# Display.net
KiCad netlist of a schematic drawn in Altium Designer
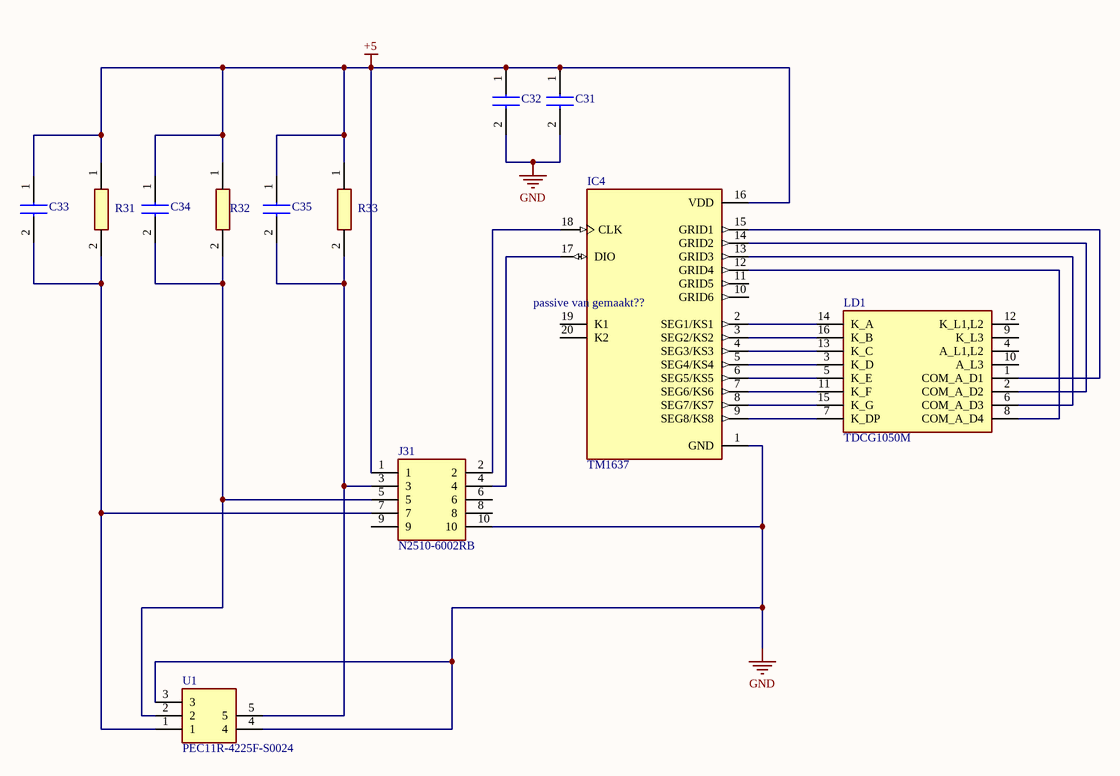
[diagram p0: Display.SchDoc]

(export (version "E")
  (design (tool "Eeschema 10.0.6"))
  (components
    (comp (ref "C31")
      (value "C0805C104K5RAC7411")
      (footprint "100nF")
      (description "Capacitor  100 uF 50VDC")
      (fields (field (name "MOUSER2 PART NUMBER") "80-C0805C104K5RACLR"))
      (libsource (lib "Schlib1") (part "C0805C104K5RAC7411"))
    )
    (comp (ref "C32")
      (value "C0805C104K5RAC7411")
      (footprint "100nF")
      (description "Capacitor  0.1 uF 50VDC")
      (fields (field (name "MOUSER2 PART NUMBER") "80-C0805C104K5RACLR"))
      (libsource (lib "Schlib1") (part "C0805C104K5RAC7411"))
    )
    (comp (ref "C33")
      (value "C0805C103K5TACAUTO")
      (footprint "10nF")
      (description "Capacitor 0.01µF 50VDC")
      (libsource (lib "Schlib1") (part "C0805C103K5TACAUTO"))
    )
    (comp (ref "C34")
      (value "C0805C103K5TACAUTO")
      (footprint "10nF")
      (description "Capacitor 0.01µF 50VDC")
      (libsource (lib "Schlib1") (part "C0805C103K5TACAUTO"))
    )
    (comp (ref "C35")
      (value "C0805C103K5TACAUTO")
      (footprint "10nF")
      (description "Capacitor 0.01µF 50VDC")
      (libsource (lib "Schlib1") (part "C0805C103K5TACAUTO"))
    )
    (comp (ref "IC4")
      (value "TM1637")
      (footprint "DisplayIC")
      (description "LED Drive Control Special Circuit")
      (fields (field (name "MF") "Titan Micro Electronics"))
      (libsource (lib "Schlib1") (part "TM1637"))
    )
    (comp (ref "J31")
      (value "N2510-6002RB")
      (footprint "SHDR10W64P254_2X5_2002X859X991P")
      (description "Connector")
      (fields (field (name "MOUSER2 PART NUMBER") "517-N2510-6002RB"))
      (libsource (lib "Schlib1") (part "N2510-6002RB"))
    )
    (comp (ref "LD1")
      (value "TDCG1050M")
      (footprint "NewPCBlib:Display")
      (description "Display")
      (fields (field (name "MOUSER2 PART NUMBER") "78-TDCG1050"))
      (libsource (lib "Schlib1") (part "TDCG1050M"))
    )
    (comp (ref "R31")
      (value "CRCW080510K0DHEAP")
      (footprint "Resistor")
      (description "Resistor 10KOhm")
      (libsource (lib "Schlib1") (part "CRCW080510K0DHEAP"))
    )
    (comp (ref "R32")
      (value "CRCW080510K0DHEAP")
      (footprint "Resistor")
      (description "Resistor 10KOhm")
      (libsource (lib "Schlib1") (part "CRCW080510K0DHEAP"))
    )
    (comp (ref "R33")
      (value "CRCW080510K0DHEAP")
      (footprint "Resistor")
      (description "Resistor 10KOhm")
      (libsource (lib "Schlib1") (part "CRCW080510K0DHEAP"))
    )
    (comp (ref "U1")
      (value "PEC11R-4225F-S0024")
      (footprint "PEC12R-4XXXF-SXXXX_1")
      (description "Undefined or Miscellaneous")
      (fields (field (name "MOUSER2 PART NUMBER") "652-PEC11R-4225F-S24"))
      (libsource (lib "Schlib1") (part "PEC11R-4225F-S0024"))
    )
  )
  (nets
    (net (code "1") (name "+5") (class "Default")
      (node (ref "C31") (pin "1") (pinfunction "1_1") (pintype "passive"))
      (node (ref "C32") (pin "1") (pinfunction "1_1") (pintype "passive"))
      (node (ref "C33") (pin "1") (pinfunction "1_1") (pintype "passive"))
      (node (ref "C34") (pin "1") (pinfunction "1_1") (pintype "passive"))
      (node (ref "C35") (pin "1") (pinfunction "1_1") (pintype "passive"))
      (node (ref "IC4") (pin "16") (pinfunction "VDD_16") (pintype "power_in"))
      (node (ref "J31") (pin "1") (pinfunction "1_1") (pintype "passive"))
      (node (ref "R31") (pin "1") (pinfunction "1_1") (pintype "passive"))
      (node (ref "R32") (pin "1") (pinfunction "1_1") (pintype "passive"))
      (node (ref "R33") (pin "1") (pinfunction "1_1") (pintype "passive"))
    )
    (net (code "2") (name "GND") (class "Default")
      (node (ref "C31") (pin "2") (pinfunction "2_2") (pintype "passive"))
      (node (ref "C32") (pin "2") (pinfunction "2_2") (pintype "passive"))
      (node (ref "IC4") (pin "1") (pinfunction "GND_1") (pintype "power_in"))
      (node (ref "J31") (pin "10") (pinfunction "10_10") (pintype "passive"))
      (node (ref "U1") (pin "3") (pinfunction "3_3") (pintype "passive"))
      (node (ref "U1") (pin "4") (pinfunction "4_4") (pintype "passive"))
    )
    (net (code "3") (name "Net-(C33-Pad2)") (class "Default")
      (node (ref "C33") (pin "2") (pinfunction "2_2") (pintype "passive"))
      (node (ref "J31") (pin "7") (pinfunction "7_7") (pintype "passive"))
      (node (ref "R31") (pin "2") (pinfunction "2_2") (pintype "passive"))
      (node (ref "U1") (pin "1") (pinfunction "1_1") (pintype "passive"))
    )
    (net (code "4") (name "Net-(C34-Pad2)") (class "Default")
      (node (ref "C34") (pin "2") (pinfunction "2_2") (pintype "passive"))
      (node (ref "J31") (pin "5") (pinfunction "5_5") (pintype "passive"))
      (node (ref "R32") (pin "2") (pinfunction "2_2") (pintype "passive"))
      (node (ref "U1") (pin "2") (pinfunction "2_2") (pintype "passive"))
    )
    (net (code "5") (name "Net-(C35-Pad2)") (class "Default")
      (node (ref "C35") (pin "2") (pinfunction "2_2") (pintype "passive"))
      (node (ref "J31") (pin "3") (pinfunction "3_3") (pintype "passive"))
      (node (ref "R33") (pin "2") (pinfunction "2_2") (pintype "passive"))
      (node (ref "U1") (pin "5") (pinfunction "5_5") (pintype "passive"))
    )
    (net (code "6") (name "Net-(IC4-CLK)") (class "Default")
      (node (ref "IC4") (pin "18") (pinfunction "CLK_18") (pintype "input"))
      (node (ref "J31") (pin "2") (pinfunction "2_2") (pintype "passive"))
    )
    (net (code "7") (name "Net-(IC4-DIO)") (class "Default")
      (node (ref "IC4") (pin "17") (pinfunction "DIO_17") (pintype "bidirectional"))
      (node (ref "J31") (pin "4") (pinfunction "4_4") (pintype "passive"))
    )
    (net (code "8") (name "Net-(IC4-GRID1)") (class "Default")
      (node (ref "IC4") (pin "15") (pinfunction "GRID1_15") (pintype "output"))
      (node (ref "LD1") (pin "1") (pinfunction "COM_A_D1_1") (pintype "passive"))
    )
    (net (code "9") (name "Net-(IC4-GRID2)") (class "Default")
      (node (ref "IC4") (pin "14") (pinfunction "GRID2_14") (pintype "output"))
      (node (ref "LD1") (pin "2") (pinfunction "COM_A_D2_2") (pintype "passive"))
    )
    (net (code "10") (name "Net-(IC4-GRID3)") (class "Default")
      (node (ref "IC4") (pin "13") (pinfunction "GRID3_13") (pintype "output"))
      (node (ref "LD1") (pin "6") (pinfunction "COM_A_D3_6") (pintype "passive"))
    )
    (net (code "11") (name "Net-(IC4-GRID4)") (class "Default")
      (node (ref "IC4") (pin "12") (pinfunction "GRID4_12") (pintype "output"))
      (node (ref "LD1") (pin "8") (pinfunction "COM_A_D4_8") (pintype "passive"))
    )
    (net (code "12") (name "Net-(IC4-SEG1{slash}KS1)") (class "Default")
      (node (ref "IC4") (pin "2") (pinfunction "SEG1/KS1_2") (pintype "output"))
      (node (ref "LD1") (pin "14") (pinfunction "K_A_14") (pintype "passive"))
    )
    (net (code "13") (name "Net-(IC4-SEG2{slash}KS2)") (class "Default")
      (node (ref "IC4") (pin "3") (pinfunction "SEG2/KS2_3") (pintype "output"))
      (node (ref "LD1") (pin "16") (pinfunction "K_B_16") (pintype "passive"))
    )
    (net (code "14") (name "Net-(IC4-SEG3{slash}KS3)") (class "Default")
      (node (ref "IC4") (pin "4") (pinfunction "SEG3/KS3_4") (pintype "output"))
      (node (ref "LD1") (pin "13") (pinfunction "K_C_13") (pintype "passive"))
    )
    (net (code "15") (name "Net-(IC4-SEG4{slash}KS4)") (class "Default")
      (node (ref "IC4") (pin "5") (pinfunction "SEG4/KS4_5") (pintype "output"))
      (node (ref "LD1") (pin "3") (pinfunction "K_D_3") (pintype "passive"))
    )
    (net (code "16") (name "Net-(IC4-SEG5{slash}KS5)") (class "Default")
      (node (ref "IC4") (pin "6") (pinfunction "SEG5/KS5_6") (pintype "output"))
      (node (ref "LD1") (pin "5") (pinfunction "K_E_5") (pintype "passive"))
    )
    (net (code "17") (name "Net-(IC4-SEG6{slash}KS6)") (class "Default")
      (node (ref "IC4") (pin "7") (pinfunction "SEG6/KS6_7") (pintype "output"))
      (node (ref "LD1") (pin "11") (pinfunction "K_F_11") (pintype "passive"))
    )
    (net (code "18") (name "Net-(IC4-SEG7{slash}KS7)") (class "Default")
      (node (ref "IC4") (pin "8") (pinfunction "SEG7/KS7_8") (pintype "output"))
      (node (ref "LD1") (pin "15") (pinfunction "K_G_15") (pintype "passive"))
    )
    (net (code "19") (name "Net-(IC4-SEG8{slash}KS8)") (class "Default")
      (node (ref "IC4") (pin "9") (pinfunction "SEG8/KS8_9") (pintype "output"))
      (node (ref "LD1") (pin "7") (pinfunction "K_DP_7") (pintype "passive"))
    )
    (net (code "20") (name "unconnected-(IC4-GRID5-Pad11)") (class "Default")
      (node (ref "IC4") (pin "11") (pinfunction "GRID5_11") (pintype "output"))
    )
    (net (code "21") (name "unconnected-(IC4-GRID6-Pad10)") (class "Default")
      (node (ref "IC4") (pin "10") (pinfunction "GRID6_10") (pintype "output"))
    )
    (net (code "22") (name "unconnected-(IC4-K1-Pad19)") (class "Default")
      (node (ref "IC4") (pin "19") (pinfunction "K1_19") (pintype "passive"))
    )
    (net (code "23") (name "unconnected-(IC4-K2-Pad20)") (class "Default")
      (node (ref "IC4") (pin "20") (pinfunction "K2_20") (pintype "passive"))
    )
    (net (code "24") (name "unconnected-(J31-Pad6)") (class "Default")
      (node (ref "J31") (pin "6") (pinfunction "6_6") (pintype "passive"))
    )
    (net (code "25") (name "unconnected-(J31-Pad8)") (class "Default")
      (node (ref "J31") (pin "8") (pinfunction "8_8") (pintype "passive"))
    )
    (net (code "26") (name "unconnected-(J31-Pad9)") (class "Default")
      (node (ref "J31") (pin "9") (pinfunction "9_9") (pintype "passive"))
    )
    (net (code "27") (name "unconnected-(LD1-A_L1,L2-Pad4)") (class "Default")
      (node (ref "LD1") (pin "4") (pinfunction "A_L1,L2_4") (pintype "passive"))
    )
    (net (code "28") (name "unconnected-(LD1-A_L3-Pad10)") (class "Default")
      (node (ref "LD1") (pin "10") (pinfunction "A_L3_10") (pintype "passive"))
    )
    (net (code "29") (name "unconnected-(LD1-K_L1,L2-Pad12)") (class "Default")
      (node (ref "LD1") (pin "12") (pinfunction "K_L1,L2_12") (pintype "passive"))
    )
    (net (code "30") (name "unconnected-(LD1-K_L3-Pad9)") (class "Default")
      (node (ref "LD1") (pin "9") (pinfunction "K_L3_9") (pintype "passive"))
    )
  )
)
